# train_gate.net
KiCad netlist of a schematic drawn in EAGLE
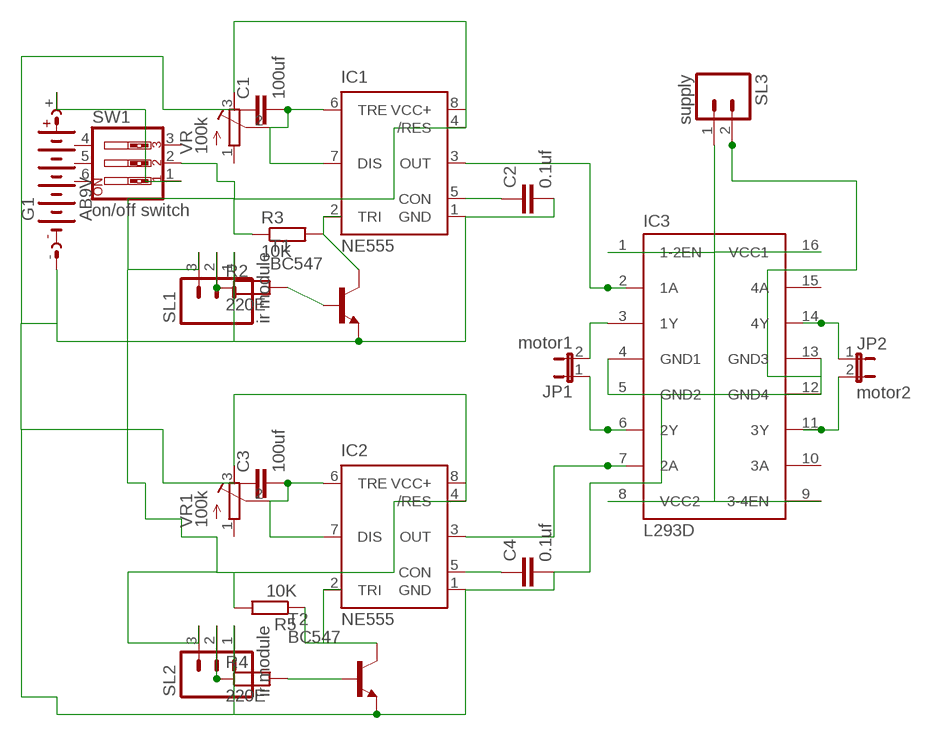
[diagram p0: schematic, sheet 1]

(export (version "E")
  (design (tool "Eeschema 10.0.6"))
  (components
    (comp (ref "C1")
      (value "100uf")
      (footprint "eagle-import:C5B7.2")
      (libsource (lib "eagle-import") (part "C5/7.2"))
    )
    (comp (ref "C2")
      (value "0.1uf")
      (footprint "eagle-import:C2.5-3")
      (libsource (lib "eagle-import") (part "C2,5-3"))
    )
    (comp (ref "C3")
      (value "100uf")
      (footprint "eagle-import:C5B7.2")
      (libsource (lib "eagle-import") (part "C5/7.2"))
    )
    (comp (ref "C4")
      (value "0.1uf")
      (footprint "eagle-import:C2.5-3")
      (libsource (lib "eagle-import") (part "C2,5-3"))
    )
    (comp (ref "G1")
      (value "AB9V")
      (footprint "eagle-import:AB9V")
      (libsource (lib "eagle-import") (part "AB9V"))
    )
    (comp (ref "IC1")
      (value "NE555")
      (footprint "eagle-import:DIL-08")
      (fields (field (name "MF") "Arrow Electronics") (field (name "MPN") "NE555N"))
      (libsource (lib "eagle-import") (part "NE555"))
    )
    (comp (ref "IC2")
      (value "NE555")
      (footprint "eagle-import:DIL-08")
      (fields (field (name "MF") "Arrow Electronics") (field (name "MPN") "NE555N"))
      (libsource (lib "eagle-import") (part "NE555"))
    )
    (comp (ref "IC3")
      (value "L293D")
      (footprint "eagle-import:DIL16")
      (libsource (lib "eagle-import") (part "L293D"))
    )
    (comp (ref "JP1")
      (value "motor1")
      (footprint "eagle-import:JP1")
      (libsource (lib "eagle-import") (part "JP1E"))
    )
    (comp (ref "JP2")
      (value "motor2")
      (footprint "eagle-import:JP1")
      (libsource (lib "eagle-import") (part "JP1E"))
    )
    (comp (ref "R2")
      (value "220E")
      (footprint "eagle-import:0204_7")
      (libsource (lib "eagle-import") (part "R-EU_0204/7"))
    )
    (comp (ref "R3")
      (value "10K")
      (footprint "eagle-import:0204_7")
      (libsource (lib "eagle-import") (part "R-EU_0204/7"))
    )
    (comp (ref "R4")
      (value "220E")
      (footprint "eagle-import:0204_7")
      (libsource (lib "eagle-import") (part "R-EU_0204/7"))
    )
    (comp (ref "R5")
      (value "10K")
      (footprint "eagle-import:0204_7")
      (libsource (lib "eagle-import") (part "R-EU_0204/7"))
    )
    (comp (ref "SL1")
      (value "ir module")
      (footprint "eagle-import:03P")
      (libsource (lib "eagle-import") (part "M03"))
    )
    (comp (ref "SL2")
      (value "ir module")
      (footprint "eagle-import:03P")
      (libsource (lib "eagle-import") (part "M03"))
    )
    (comp (ref "SL3")
      (value "supply")
      (footprint "eagle-import:02P")
      (libsource (lib "eagle-import") (part "M02"))
    )
    (comp (ref "SW1")
      (value "on/off switch")
      (footprint "eagle-import:EDG-03")
      (libsource (lib "eagle-import") (part "SW_DIP-3"))
    )
    (comp (ref "T1")
      (value "BC547")
      (footprint "eagle-import:TO92")
      (libsource (lib "eagle-import") (part "BC547"))
    )
    (comp (ref "T2")
      (value "BC547")
      (footprint "eagle-import:TO92")
      (libsource (lib "eagle-import") (part "BC547"))
    )
    (comp (ref "VR")
      (value "100k")
      (footprint "eagle-import:RTRIM64P")
      (libsource (lib "eagle-import") (part "R-TRIMM64P"))
    )
    (comp (ref "VR1")
      (value "100k")
      (footprint "eagle-import:RTRIM64P")
      (libsource (lib "eagle-import") (part "R-TRIMM64P"))
    )
  )
  (nets
    (net (code "1") (name "Net-(G1-Pad+)") (class "Default")
      (node (ref "G1") (pin "+") (pinfunction "+_+") (pintype "passive"))
      (node (ref "SW1") (pin "1") (pinfunction "1_1") (pintype "passive"))
    )
    (net (code "2") (name "Net-(IC1-CON)") (class "Default")
      (node (ref "C2") (pin "1") (pinfunction "1_1") (pintype "passive"))
      (node (ref "IC1") (pin "5") (pinfunction "CON_5") (pintype "input"))
    )
    (net (code "3") (name "Net-(IC1-DIS)") (class "Default")
      (node (ref "C1") (pin "2") (pinfunction "2_2") (pintype "passive"))
      (node (ref "IC1") (pin "6") (pinfunction "TRE_6") (pintype "input"))
      (node (ref "IC1") (pin "7") (pinfunction "DIS_7") (pintype "input"))
      (node (ref "VR") (pin "2") (pinfunction "S_2") (pintype "passive"))
    )
    (net (code "4") (name "Net-(IC1-GND)") (class "Default")
      (node (ref "C1") (pin "1") (pinfunction "1_1") (pintype "passive"))
      (node (ref "C2") (pin "2") (pinfunction "2_2") (pintype "passive"))
      (node (ref "C3") (pin "1") (pinfunction "1_1") (pintype "passive"))
      (node (ref "C4") (pin "2") (pinfunction "2_2") (pintype "passive"))
      (node (ref "G1") (pin "-") (pinfunction "-_-") (pintype "passive"))
      (node (ref "IC1") (pin "1") (pinfunction "GND_1") (pintype "power_in"))
      (node (ref "IC2") (pin "1") (pinfunction "GND_1") (pintype "power_in"))
      (node (ref "IC3") (pin "12") (pinfunction "GND4_12") (pintype "power_in"))
      (node (ref "IC3") (pin "13") (pinfunction "GND3_13") (pintype "power_in"))
      (node (ref "IC3") (pin "4") (pinfunction "GND1_4") (pintype "power_in"))
      (node (ref "IC3") (pin "5") (pinfunction "GND2_5") (pintype "power_in"))
      (node (ref "SL1") (pin "1") (pinfunction "1_1") (pintype "passive"))
      (node (ref "SL2") (pin "1") (pinfunction "1_1") (pintype "passive"))
      (node (ref "SL3") (pin "2") (pinfunction "2_2") (pintype "passive"))
      (node (ref "T1") (pin "1") (pinfunction "E_1") (pintype "passive"))
      (node (ref "T2") (pin "1") (pinfunction "E_1") (pintype "passive"))
    )
    (net (code "5") (name "Net-(IC1-OUT)") (class "Default")
      (node (ref "IC1") (pin "3") (pinfunction "OUT_3") (pintype "output"))
      (node (ref "IC3") (pin "2") (pinfunction "1A_2") (pintype "input"))
    )
    (net (code "6") (name "Net-(IC1-TRI)") (class "Default")
      (node (ref "IC1") (pin "2") (pinfunction "TRI_2") (pintype "input"))
      (node (ref "R3") (pin "2") (pinfunction "2_2") (pintype "passive"))
      (node (ref "T1") (pin "3") (pinfunction "C_3") (pintype "passive"))
    )
    (net (code "7") (name "Net-(IC1-VCC+)") (class "Default")
      (node (ref "IC1") (pin "4") (pinfunction "/RES_4") (pintype "input"))
      (node (ref "IC1") (pin "8") (pinfunction "VCC+_8") (pintype "power_in"))
      (node (ref "IC2") (pin "4") (pinfunction "/RES_4") (pintype "input"))
      (node (ref "IC2") (pin "8") (pinfunction "VCC+_8") (pintype "power_in"))
      (node (ref "R3") (pin "1") (pinfunction "1_1") (pintype "passive"))
      (node (ref "R5") (pin "2") (pinfunction "2_2") (pintype "passive"))
      (node (ref "SL1") (pin "3") (pinfunction "3_3") (pintype "passive"))
      (node (ref "SL2") (pin "3") (pinfunction "3_3") (pintype "passive"))
      (node (ref "SW1") (pin "2") (pinfunction "2_2") (pintype "passive"))
      (node (ref "VR") (pin "3") (pinfunction "A_3") (pintype "passive"))
      (node (ref "VR1") (pin "3") (pinfunction "A_3") (pintype "passive"))
    )
    (net (code "8") (name "Net-(IC2-CON)") (class "Default")
      (node (ref "C4") (pin "1") (pinfunction "1_1") (pintype "passive"))
      (node (ref "IC2") (pin "5") (pinfunction "CON_5") (pintype "input"))
    )
    (net (code "9") (name "Net-(IC2-DIS)") (class "Default")
      (node (ref "C3") (pin "2") (pinfunction "2_2") (pintype "passive"))
      (node (ref "IC2") (pin "6") (pinfunction "TRE_6") (pintype "input"))
      (node (ref "IC2") (pin "7") (pinfunction "DIS_7") (pintype "input"))
      (node (ref "VR1") (pin "2") (pinfunction "S_2") (pintype "passive"))
    )
    (net (code "10") (name "Net-(IC2-OUT)") (class "Default")
      (node (ref "IC2") (pin "3") (pinfunction "OUT_3") (pintype "output"))
      (node (ref "IC3") (pin "7") (pinfunction "2A_7") (pintype "input"))
    )
    (net (code "11") (name "Net-(IC2-TRI)") (class "Default")
      (node (ref "IC2") (pin "2") (pinfunction "TRI_2") (pintype "input"))
      (node (ref "R5") (pin "1") (pinfunction "1_1") (pintype "passive"))
      (node (ref "T2") (pin "3") (pinfunction "C_3") (pintype "passive"))
    )
    (net (code "12") (name "Net-(IC3-1-2EN)") (class "Default")
      (node (ref "IC3") (pin "1") (pinfunction "1-2EN_1") (pintype "input"))
      (node (ref "IC3") (pin "16") (pinfunction "VCC1_16") (pintype "power_in"))
      (node (ref "IC3") (pin "8") (pinfunction "VCC2_8") (pintype "power_in"))
      (node (ref "IC3") (pin "9") (pinfunction "3-4EN_9") (pintype "input"))
      (node (ref "SL3") (pin "1") (pinfunction "1_1") (pintype "passive"))
    )
    (net (code "13") (name "Net-(IC3-1Y)") (class "Default")
      (node (ref "IC3") (pin "3") (pinfunction "1Y_3") (pintype "output"))
      (node (ref "JP1") (pin "2") (pinfunction "2_2") (pintype "passive"))
    )
    (net (code "14") (name "Net-(IC3-2Y)") (class "Default")
      (node (ref "IC3") (pin "6") (pinfunction "2Y_6") (pintype "output"))
      (node (ref "JP1") (pin "1") (pinfunction "1_1") (pintype "passive"))
    )
    (net (code "15") (name "Net-(IC3-3Y)") (class "Default")
      (node (ref "IC3") (pin "11") (pinfunction "3Y_11") (pintype "output"))
      (node (ref "JP2") (pin "2") (pinfunction "2_2") (pintype "passive"))
    )
    (net (code "16") (name "Net-(IC3-4Y)") (class "Default")
      (node (ref "IC3") (pin "14") (pinfunction "4Y_14") (pintype "output"))
      (node (ref "JP2") (pin "1") (pinfunction "1_1") (pintype "passive"))
    )
    (net (code "17") (name "Net-(R2-Pad1)") (class "Default")
      (node (ref "R2") (pin "1") (pinfunction "1_1") (pintype "passive"))
      (node (ref "SL1") (pin "2") (pinfunction "2_2") (pintype "passive"))
    )
    (net (code "18") (name "Net-(R4-Pad1)") (class "Default")
      (node (ref "R4") (pin "1") (pinfunction "1_1") (pintype "passive"))
      (node (ref "SL2") (pin "2") (pinfunction "2_2") (pintype "passive"))
    )
    (net (code "19") (name "Net-(T1-B)") (class "Default")
      (node (ref "R2") (pin "2") (pinfunction "2_2") (pintype "passive"))
      (node (ref "T1") (pin "2") (pinfunction "B_2") (pintype "passive"))
    )
    (net (code "20") (name "Net-(T2-B)") (class "Default")
      (node (ref "R4") (pin "2") (pinfunction "2_2") (pintype "passive"))
      (node (ref "T2") (pin "2") (pinfunction "B_2") (pintype "passive"))
    )
    (net (code "21") (name "unconnected-(IC3-3A-Pad10)") (class "Default")
      (node (ref "IC3") (pin "10") (pinfunction "3A_10") (pintype "input"))
    )
    (net (code "22") (name "unconnected-(IC3-4A-Pad15)") (class "Default")
      (node (ref "IC3") (pin "15") (pinfunction "4A_15") (pintype "input"))
    )
    (net (code "23") (name "unconnected-(SW1-Pad3)") (class "Default")
      (node (ref "SW1") (pin "3") (pinfunction "3_3") (pintype "passive"))
    )
    (net (code "24") (name "unconnected-(SW1-Pad4)") (class "Default")
      (node (ref "SW1") (pin "4") (pinfunction "4_4") (pintype "passive"))
    )
    (net (code "25") (name "unconnected-(SW1-Pad5)") (class "Default")
      (node (ref "SW1") (pin "5") (pinfunction "5_5") (pintype "passive"))
    )
    (net (code "26") (name "unconnected-(SW1-Pad6)") (class "Default")
      (node (ref "SW1") (pin "6") (pinfunction "6_6") (pintype "passive"))
    )
    (net (code "27") (name "unconnected-(VR-E-Pad1)") (class "Default")
      (node (ref "VR") (pin "1") (pinfunction "E_1") (pintype "passive"))
    )
    (net (code "28") (name "unconnected-(VR1-E-Pad1)") (class "Default")
      (node (ref "VR1") (pin "1") (pinfunction "E_1") (pintype "passive"))
    )
  )
)
